# Buck_converter.net
KiCad netlist of a schematic drawn in Altium Designer
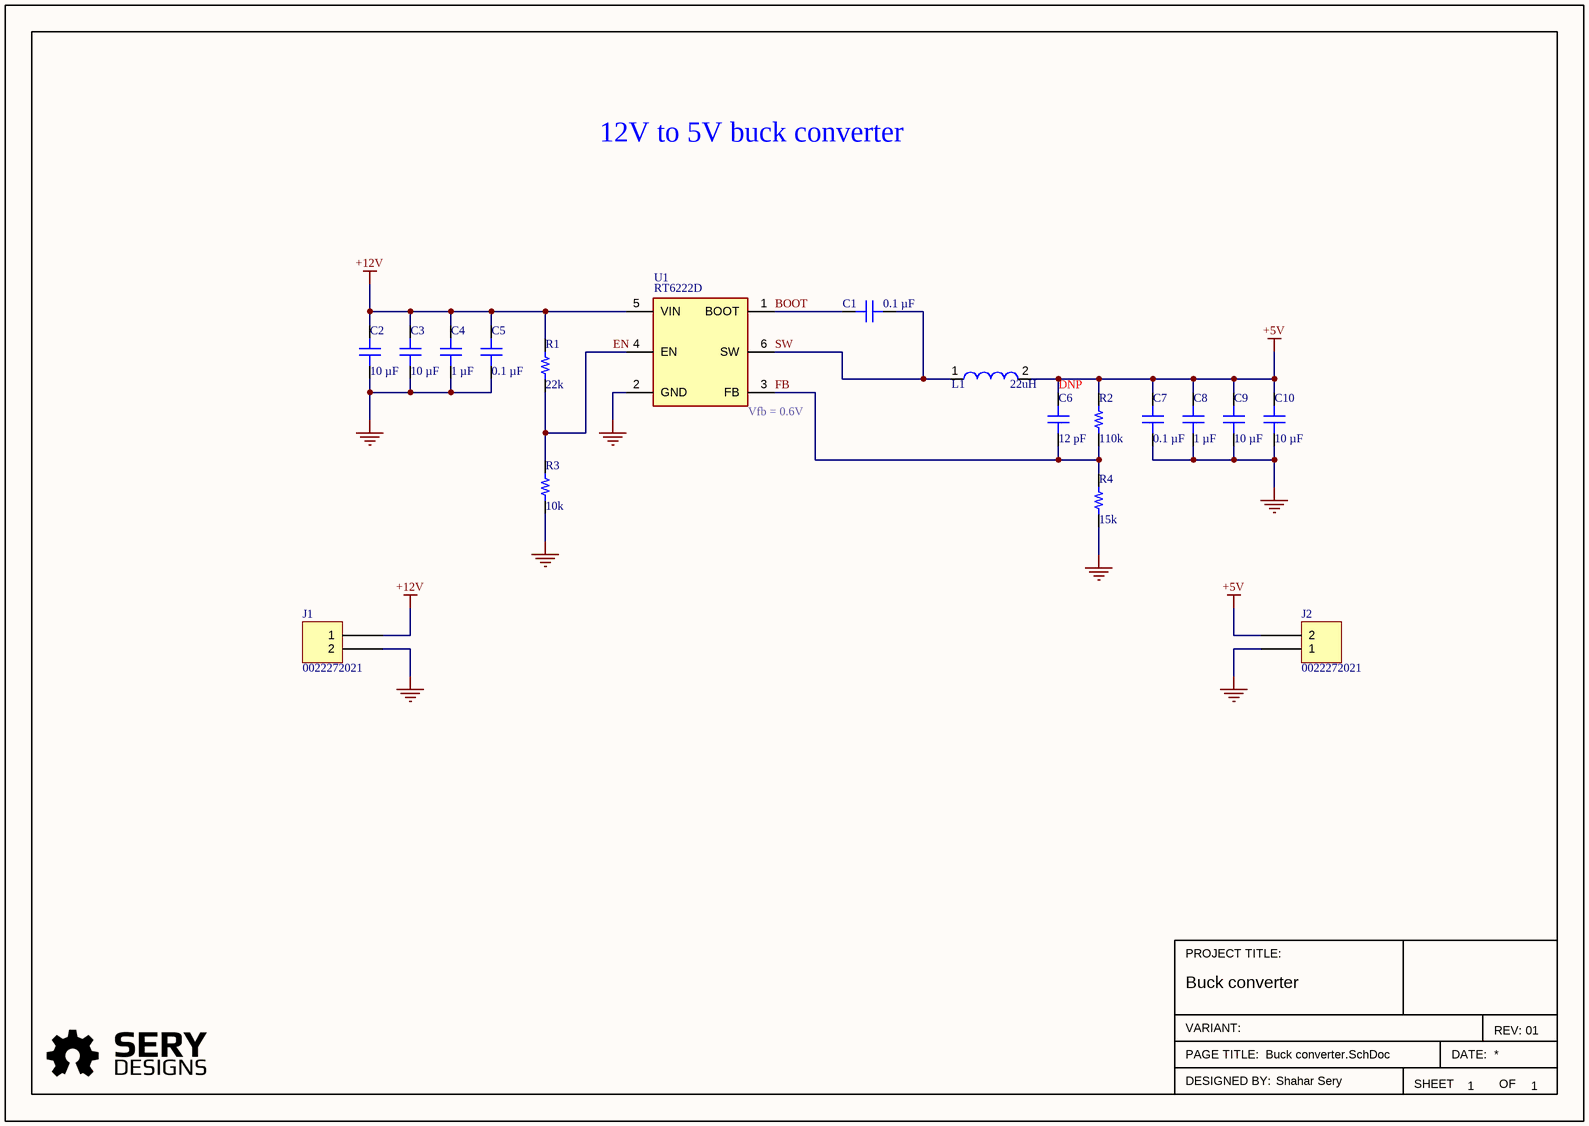
[diagram p0: Buck converter.SchDoc]

(export (version "E")
  (design (tool "Eeschema 10.0.6"))
  (components
    (comp (ref "C1")
      (value "0.1 µF")
      (footprint "CAP 0402_1005")
      (description "CAP CER 0.1UF 50V X7R 0402")
      (fields
        (field (name "PART NUMBER") "GRT155R71H104KE01D")
        (field (name "MANUFACTURER") "Murata Electronics")
      )
      (libsource (lib "Celestial Altium Library - altium_library") (part "Capacitor"))
    )
    (comp (ref "C2")
      (value "10 µF")
      (footprint "CAP 0805_2012")
      (description "CAP CER 10UF 50V X5R 0805")
      (fields
        (field (name "PART NUMBER") "GRM21BR61H106ME43L")
        (field (name "MANUFACTURER") "Murata Electronics")
      )
      (libsource (lib "Celestial Altium Library - altium_library") (part "Capacitor"))
    )
    (comp (ref "C3")
      (value "10 µF")
      (footprint "CAP 0805_2012")
      (description "CAP CER 10UF 50V X5R 0805")
      (fields
        (field (name "PART NUMBER") "GRM21BR61H106ME43L")
        (field (name "MANUFACTURER") "Murata Electronics")
      )
      (libsource (lib "Celestial Altium Library - altium_library") (part "Capacitor"))
    )
    (comp (ref "C4")
      (value "1 µF")
      (footprint "CAP 0603_1608")
      (description "CAP CER 1UF 50V X7R 0603")
      (fields (field (name "PART NUMBER") "UMK107AB7105KA-T") (field (name "MANUFACTURER") "Taiyo Yuden"))
      (libsource (lib "Celestial Altium Library - altium_library") (part "Capacitor"))
    )
    (comp (ref "C5")
      (value "0.1 µF")
      (footprint "CAP 0402_1005")
      (description "CAP CER 0.1UF 50V X7R 0402")
      (fields
        (field (name "PART NUMBER") "GRT155R71H104KE01D")
        (field (name "MANUFACTURER") "Murata Electronics")
      )
      (libsource (lib "Celestial Altium Library - altium_library") (part "Capacitor"))
    )
    (comp (ref "C6")
      (value "12 pF")
      (footprint "CAP 0402_1005")
      (description "CAP CER 12PF 50V C0G/NP0 0402")
      (fields
        (field (name "PART NUMBER") "GCM1555C1H120JA16D")
        (field (name "MANUFACTURER") "Murata Electronics")
      )
      (libsource (lib "Celestial Altium Library - altium_library") (part "Capacitor"))
    )
    (comp (ref "C7")
      (value "0.1 µF")
      (footprint "CAP 0402_1005")
      (description "CAP CER 0.1UF 50V X7R 0402")
      (fields
        (field (name "PART NUMBER") "GRT155R71H104KE01D")
        (field (name "MANUFACTURER") "Murata Electronics")
      )
      (libsource (lib "Celestial Altium Library - altium_library") (part "Capacitor"))
    )
    (comp (ref "C8")
      (value "1 µF")
      (footprint "CAP 0603_1608")
      (description "CAP CER 1UF 50V X7R 0603")
      (fields (field (name "PART NUMBER") "UMK107AB7105KA-T") (field (name "MANUFACTURER") "Taiyo Yuden"))
      (libsource (lib "Celestial Altium Library - altium_library") (part "Capacitor"))
    )
    (comp (ref "C9")
      (value "10 µF")
      (footprint "CAP 0805_2012")
      (description "CAP CER 10UF 50V X5R 0805")
      (fields
        (field (name "PART NUMBER") "GRM21BR61H106ME43L")
        (field (name "MANUFACTURER") "Murata Electronics")
      )
      (libsource (lib "Celestial Altium Library - altium_library") (part "Capacitor"))
    )
    (comp (ref "C10")
      (value "10 µF")
      (footprint "CAP 0805_2012")
      (description "CAP CER 10UF 50V X5R 0805")
      (fields
        (field (name "PART NUMBER") "GRM21BR61H106ME43L")
        (field (name "MANUFACTURER") "Murata Electronics")
      )
      (libsource (lib "Celestial Altium Library - altium_library") (part "Capacitor"))
    )
    (comp (ref "J1")
      (value "0022272021")
      (footprint "MOLEX KK 0022272021")
      (description "CONN HEADER VERT 2POS 2.54MM")
      (fields (field (name "MANUFACTURER") "Molex"))
      (libsource (lib "Celestial Altium Library - altium_library") (part "2 Pin"))
    )
    (comp (ref "J2")
      (value "0022272021")
      (footprint "MOLEX KK 0022272021")
      (description "CONN HEADER VERT 2POS 2.54MM")
      (fields (field (name "MANUFACTURER") "Molex"))
      (libsource (lib "") (part "2 Pin_1"))
    )
    (comp (ref "L1")
      (value "22uH")
      (footprint "Inductors:NRS8040T220MJGJV")
      (description "Inductor, Fixed, SMD, 22µH, 2.2A")
      (fields (field (name "PART NUMBER") "6006M0220F000") (field (name "MF") "Taiyo Yuden"))
      (libsource (lib "Inductors") (part "NRS8040T220MJGJV"))
    )
    (comp (ref "OSHW-logo1")
      (value "OSHW-logo")
      (footprint "Fabricated:OSHW-logo")
      (description "OSHW logo, no writing")
      (libsource (lib "Fabricated") (part "OSHW-logo"))
    )
    (comp (ref "R1")
      (value "22k")
      (footprint "RES 0402_1005")
      (description "RES SMD 22K OHM 1% 1/16W 0402")
      (fields (field (name "PART NUMBER") "CR0402-FX-2202GLF") (field (name "MANUFACTURER") "Bourns Inc."))
      (libsource (lib "Celestial Altium Library - altium_library") (part "Resistor"))
    )
    (comp (ref "R2")
      (value "110k")
      (footprint "RES 0402_1005")
      (description "RES SMD 110K OHM 1% 1/16W 0402")
      (fields (field (name "PART NUMBER") "AF0402FR-07110KL") (field (name "MANUFACTURER") "Yageo"))
      (libsource (lib "Celestial Altium Library - altium_library") (part "Resistor"))
    )
    (comp (ref "R3")
      (value "10k")
      (footprint "RES 0402_1005")
      (description "RES SMD 10K OHM 1% 1/16W 0402")
      (fields (field (name "PART NUMBER") "RE0402FRE0710KL") (field (name "MANUFACTURER") "Yageo"))
      (libsource (lib "Celestial Altium Library - altium_library") (part "Resistor"))
    )
    (comp (ref "R4")
      (value "15k")
      (footprint "RES 0402_1005")
      (description "RES SMD 15K OHM 1% 1/16W 0402")
      (fields (field (name "PART NUMBER") "CRCW040215K0FKED") (field (name "MANUFACTURER") "Vishay Dale"))
      (libsource (lib "Celestial Altium Library - altium_library") (part "Resistor"))
    )
    (comp (ref "SeryDesigns-logo1")
      (value "SeryDesigns-logo")
      (footprint "Fabricated:SeryDesigns-logo")
      (description "Sery designs logo")
      (libsource (lib "Fabricated") (part "SeryDesigns-logo"))
    )
    (comp (ref "U1")
      (value "RT6222D")
      (footprint "ICs:sot23-6")
      (description "IC, SMD, 2A, 1.4MHz,  Synchronous Buck Converter, SOT-23-6")
      (fields (field (name "MF") "SGMicro") (field (name "MPN") "SGM61410"))
      (libsource (lib "ICs") (part "RT6222D"))
    )
  )
  (nets
    (net (code "1") (name "+5V") (class "Default")
      (node (ref "C10") (pin "2") (pinfunction "2_2") (pintype "passive"))
      (node (ref "C6") (pin "2") (pinfunction "2_2") (pintype "passive"))
      (node (ref "C7") (pin "2") (pinfunction "2_2") (pintype "passive"))
      (node (ref "C8") (pin "2") (pinfunction "2_2") (pintype "passive"))
      (node (ref "C9") (pin "2") (pinfunction "2_2") (pintype "passive"))
      (node (ref "J2") (pin "2") (pinfunction "2_2") (pintype "passive"))
      (node (ref "L1") (pin "2") (pinfunction "2_2") (pintype "passive"))
      (node (ref "R2") (pin "2") (pinfunction "2_2") (pintype "passive"))
    )
    (net (code "2") (name "+12V") (class "Default")
      (node (ref "C2") (pin "2") (pinfunction "2_2") (pintype "passive"))
      (node (ref "C3") (pin "2") (pinfunction "2_2") (pintype "passive"))
      (node (ref "C4") (pin "2") (pinfunction "2_2") (pintype "passive"))
      (node (ref "C5") (pin "2") (pinfunction "2_2") (pintype "passive"))
      (node (ref "J1") (pin "1") (pinfunction "1_1") (pintype "passive"))
      (node (ref "R1") (pin "2") (pinfunction "2_2") (pintype "passive"))
      (node (ref "U1") (pin "5") (pinfunction "VIN_5") (pintype "passive"))
    )
    (net (code "3") (name "/BOOT") (class "Default")
      (node (ref "C1") (pin "2") (pinfunction "2_2") (pintype "passive"))
      (node (ref "U1") (pin "1") (pinfunction "BOOT_1") (pintype "passive"))
    )
    (net (code "4") (name "/EN") (class "Default")
      (node (ref "R1") (pin "1") (pinfunction "1_1") (pintype "passive"))
      (node (ref "R3") (pin "2") (pinfunction "2_2") (pintype "passive"))
      (node (ref "U1") (pin "4") (pinfunction "EN_4") (pintype "passive"))
    )
    (net (code "5") (name "/FB") (class "Default")
      (node (ref "C6") (pin "1") (pinfunction "1_1") (pintype "passive"))
      (node (ref "R2") (pin "1") (pinfunction "1_1") (pintype "passive"))
      (node (ref "R4") (pin "2") (pinfunction "2_2") (pintype "passive"))
      (node (ref "U1") (pin "3") (pinfunction "FB_3") (pintype "passive"))
    )
    (net (code "6") (name "/SW") (class "Default")
      (node (ref "C1") (pin "1") (pinfunction "1_1") (pintype "passive"))
      (node (ref "L1") (pin "1") (pinfunction "1_1") (pintype "passive"))
      (node (ref "U1") (pin "6") (pinfunction "SW_6") (pintype "passive"))
    )
    (net (code "7") (name "GND") (class "Default")
      (node (ref "C10") (pin "1") (pinfunction "1_1") (pintype "passive"))
      (node (ref "C2") (pin "1") (pinfunction "1_1") (pintype "passive"))
      (node (ref "C3") (pin "1") (pinfunction "1_1") (pintype "passive"))
      (node (ref "C4") (pin "1") (pinfunction "1_1") (pintype "passive"))
      (node (ref "C5") (pin "1") (pinfunction "1_1") (pintype "passive"))
      (node (ref "C7") (pin "1") (pinfunction "1_1") (pintype "passive"))
      (node (ref "C8") (pin "1") (pinfunction "1_1") (pintype "passive"))
      (node (ref "C9") (pin "1") (pinfunction "1_1") (pintype "passive"))
      (node (ref "J1") (pin "2") (pinfunction "2_2") (pintype "passive"))
      (node (ref "J2") (pin "1") (pinfunction "1_1") (pintype "passive"))
      (node (ref "R3") (pin "1") (pinfunction "1_1") (pintype "passive"))
      (node (ref "R4") (pin "1") (pinfunction "1_1") (pintype "passive"))
      (node (ref "U1") (pin "2") (pinfunction "GND_2") (pintype "passive"))
    )
  )
)
